# High_Pass_Filter.net
KiCad netlist of a schematic drawn in EasyEDA Pro
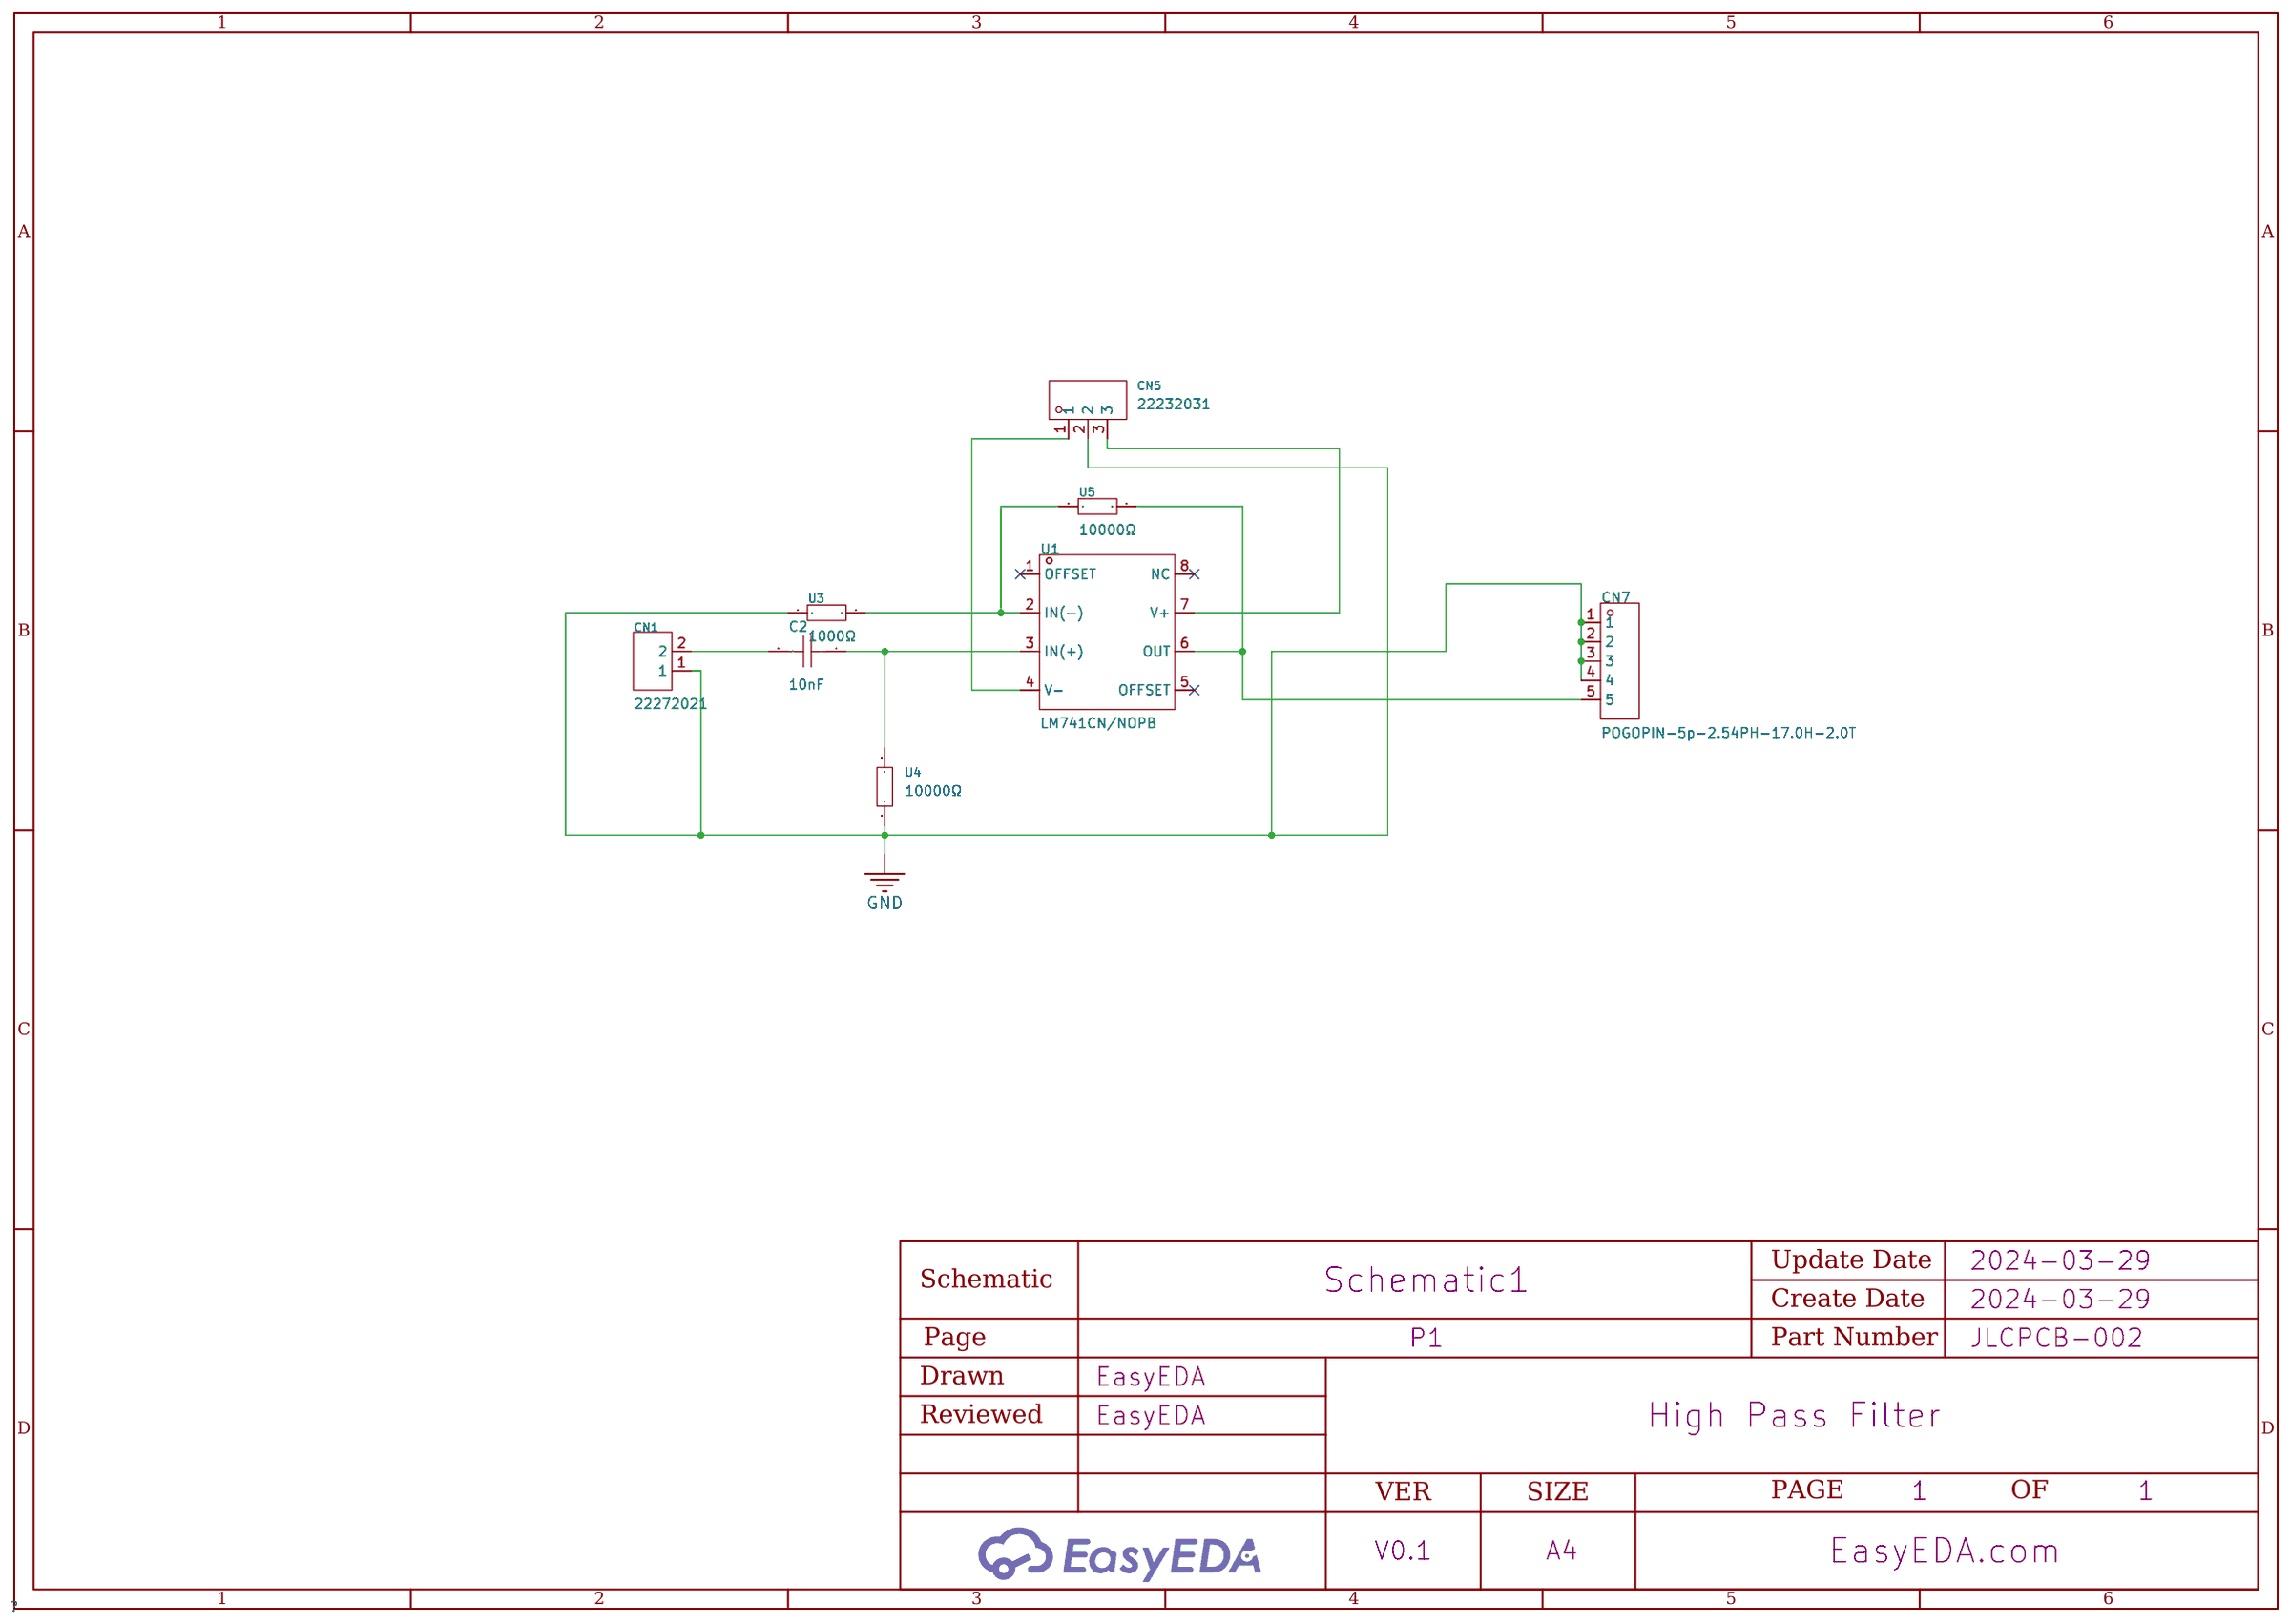
[diagram p0: schematic sheet]

(export (version "E")
  (design (tool "Eeschema 10.0.6"))
  (components
    (comp (ref "C2")
      (value "10nF")
      (footprint "easyedapro:C0603")
      (libsource (lib "easyedapro") (part "CAP"))
    )
    (comp (ref "CN1")
      (value "22272021")
      (footprint "easyedapro:CONN-TH_22272021")
      (fields (field (name "Manufacturer") "MOLEX"))
      (libsource (lib "easyedapro") (part "22272021"))
    )
    (comp (ref "CN5")
      (value "22232031")
      (footprint "easyedapro:CONN-TH_3P-P2.54_22-23-2031")
      (fields (field (name "Manufacturer") "MOLEX"))
      (libsource (lib "easyedapro") (part "22-23-2031"))
    )
    (comp (ref "CN7")
      (value "POGOPIN-5p-2.54PH-17.0H-2.0T")
      (footprint "easyedapro:CONN-TH_5P-P2.54_POGOPIN-5P-2.54P")
      (libsource (lib "easyedapro") (part "POGOPIN-5P-2.54PH-17.0H-2.0T"))
    )
    (comp (ref "U1")
      (value "LM741CN/NOPB")
      (footprint "easyedapro:DIP-8_L9.8-W6.6-P2.54-LS7.6-BL")
      (fields (field (name "Manufacturer") "TI(德州仪器)"))
      (libsource (lib "easyedapro") (part "LM741CN"))
    )
    (comp (ref "U3")
      (value "1000Ω")
      (footprint "easyedapro:RES-TH_BD3.5-L9.0-P13.00-D0.8")
      (description "Type:Safety Resistor Resistance: Tolerance:±5% Tolerance:±5% Power(Watts):1W")
      (fields (field (name "Manufacturer Part") "FR1WS-5.1Ω±5%") (field (name "Manufacturer") "CCO(千志电子)"))
      (libsource (lib "easyedapro") (part "FR1WS-5.1Ω±5%"))
    )
    (comp (ref "U4")
      (value "10000Ω")
      (footprint "easyedapro:RES-TH_BD3.5-L9.0-P13.00-D0.8")
      (description "Type:Safety Resistor Resistance: Tolerance:±5% Tolerance:±5% Power(Watts):1W")
      (fields (field (name "Manufacturer Part") "FR1WS-5.1Ω±5%") (field (name "Manufacturer") "CCO(千志电子)"))
      (libsource (lib "easyedapro") (part "FR1WS-5.1Ω±5%"))
    )
    (comp (ref "U5")
      (value "10000Ω")
      (footprint "easyedapro:RES-TH_BD3.5-L9.0-P13.00-D0.8")
      (description "Type:Safety Resistor Resistance: Tolerance:±5% Tolerance:±5% Power(Watts):1W")
      (fields (field (name "Manufacturer Part") "FR1WS-5.1Ω±5%") (field (name "Manufacturer") "CCO(千志电子)"))
      (libsource (lib "easyedapro") (part "FR1WS-5.1Ω±5%"))
    )
  )
  (nets
    (net (code "1") (name "GND") (class "Default")
      (node (ref "CN1") (pin "1") (pinfunction "1_1") (pintype "input"))
      (node (ref "CN5") (pin "2") (pinfunction "2_2") (pintype "input"))
      (node (ref "CN7") (pin "1") (pinfunction "1_1") (pintype "input"))
      (node (ref "CN7") (pin "2") (pinfunction "2_2") (pintype "input"))
      (node (ref "CN7") (pin "3") (pinfunction "3_3") (pintype "input"))
      (node (ref "CN7") (pin "4") (pinfunction "4_4") (pintype "input"))
      (node (ref "U3") (pin "1") (pinfunction "1_1") (pintype "input"))
      (node (ref "U4") (pin "1") (pinfunction "1_1") (pintype "input"))
    )
    (net (code "2") (name "Net-(C2-Pad2)") (class "Default")
      (node (ref "C2") (pin "2") (pinfunction "2_2") (pintype "input"))
      (node (ref "CN1") (pin "2") (pinfunction "2_2") (pintype "input"))
    )
    (net (code "3") (name "Net-(U1-IN(+))") (class "Default")
      (node (ref "C2") (pin "1") (pinfunction "1_1") (pintype "input"))
      (node (ref "U1") (pin "3") (pinfunction "IN(+)_3") (pintype "input"))
      (node (ref "U4") (pin "2") (pinfunction "2_2") (pintype "input"))
    )
    (net (code "4") (name "Net-(U1-IN(-))") (class "Default")
      (node (ref "U1") (pin "2") (pinfunction "IN(-)_2") (pintype "input"))
      (node (ref "U3") (pin "2") (pinfunction "2_2") (pintype "input"))
      (node (ref "U5") (pin "1") (pinfunction "1_1") (pintype "input"))
    )
    (net (code "5") (name "Net-(U1-OUT)") (class "Default")
      (node (ref "CN7") (pin "5") (pinfunction "5_5") (pintype "input"))
      (node (ref "U1") (pin "6") (pinfunction "OUT_6") (pintype "input"))
      (node (ref "U5") (pin "2") (pinfunction "2_2") (pintype "input"))
    )
    (net (code "6") (name "Net-(U1-V+)") (class "Default")
      (node (ref "CN5") (pin "3") (pinfunction "3_3") (pintype "input"))
      (node (ref "U1") (pin "7") (pinfunction "V+_7") (pintype "input"))
    )
    (net (code "7") (name "Net-(U1-V-)") (class "Default")
      (node (ref "CN5") (pin "1") (pinfunction "1_1") (pintype "input"))
      (node (ref "U1") (pin "4") (pinfunction "V-_4") (pintype "input"))
    )
    (net (code "8") (name "unconnected-(U1-NC-Pad8)") (class "Default")
      (node (ref "U1") (pin "8") (pinfunction "NC_8") (pintype "input+no_connect"))
    )
    (net (code "9") (name "unconnected-(U1-OFFSET-Pad1)") (class "Default")
      (node (ref "U1") (pin "1") (pinfunction "OFFSET_1") (pintype "input+no_connect"))
    )
    (net (code "10") (name "unconnected-(U1-OFFSET-Pad5)") (class "Default")
      (node (ref "U1") (pin "5") (pinfunction "OFFSET_5") (pintype "input+no_connect"))
    )
  )
)
